# Sumo_Motor_Stepper_DC_Conns.net
KiCad netlist of a schematic drawn in Altium Designer
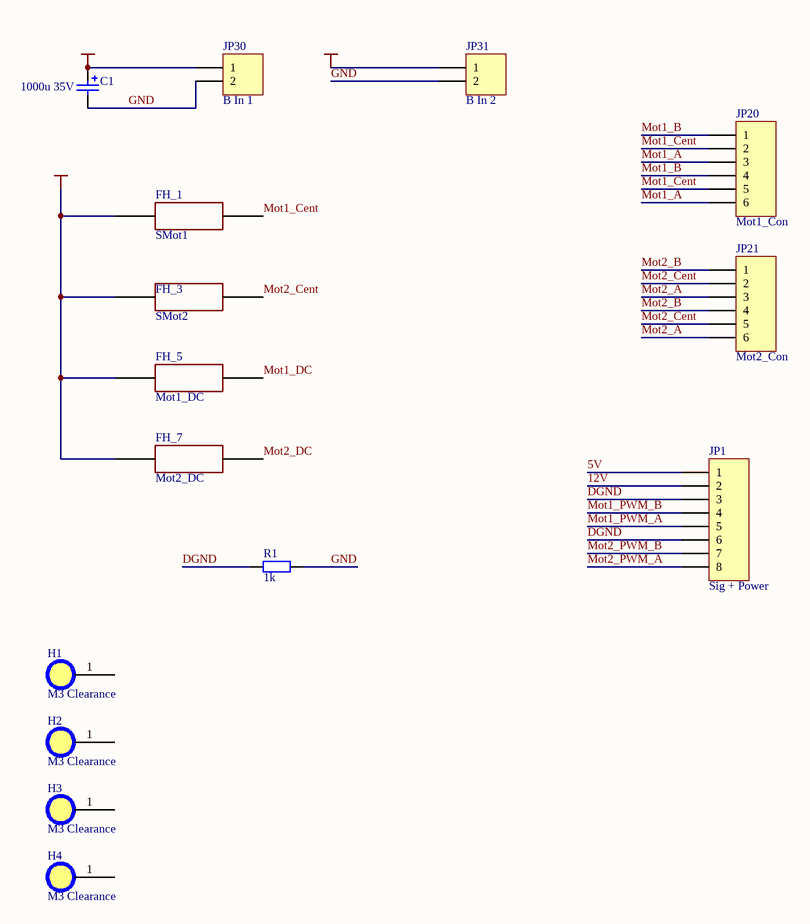
[diagram p0: Sumo_Motor_Stepper_DC_Conns.SCHDOC]

(export (version "E")
  (design (tool "Eeschema 10.0.6"))
  (components
    (comp (ref "C1")
      (value "1000u 35V")
      (footprint "CAPPOL7.5-16")
      (description "Polarized Capacitor (Radial)")
      (fields (field (name "Comment") "Cap Pol1") (field (name "PUBLISHER") "Altium Limited"))
      (libsource (lib "Miscellaneous Devices") (part "Cap Pol1"))
    )
    (comp (ref "FH_1")
      (value "SMot1")
      (footprint "FuseHolder Miniblade")
      (description "Fuse Holder")
      (libsource (lib "Sumo") (part "Fuse_Holder"))
    )
    (comp (ref "FH_3")
      (value "SMot2")
      (footprint "FuseHolder Miniblade")
      (description "Fuse Holder")
      (libsource (lib "Sumo") (part "Fuse_Holder"))
    )
    (comp (ref "FH_5")
      (value "Mot1_DC")
      (footprint "FuseHolder Miniblade")
      (description "Fuse Holder")
      (libsource (lib "") (part "Fuse_Holder_1"))
    )
    (comp (ref "FH_7")
      (value "Mot2_DC")
      (footprint "FuseHolder Miniblade")
      (libsource (lib "") (part "Fuse_Holder_1"))
    )
    (comp (ref "H1")
      (value "M3 Clearance")
      (footprint "M3 Clearance")
      (description "3.2mm ID clearance hole for M3 screw")
      (libsource (lib "Sumo") (part "M3 Clearance hole"))
    )
    (comp (ref "H2")
      (value "M3 Clearance")
      (footprint "M3 Clearance")
      (description "3.2mm ID clearance hole for M3 screw")
      (libsource (lib "Sumo") (part "M3 Clearance hole"))
    )
    (comp (ref "H3")
      (value "M3 Clearance")
      (footprint "M3 Clearance")
      (description "3.2mm ID clearance hole for M3 screw")
      (libsource (lib "Sumo") (part "M3 Clearance hole"))
    )
    (comp (ref "H4")
      (value "M3 Clearance")
      (footprint "M3 Clearance")
      (description "3.2mm ID clearance hole for M3 screw")
      (libsource (lib "Sumo") (part "M3 Clearance hole"))
    )
    (comp (ref "JP1")
      (value "Sig + Power")
      (footprint "PHR 1x8 2mm")
      (description "Header, 8-Pin")
      (fields (field (name "PUBLISHER") "Altium Limited"))
      (libsource (lib "Miscellaneous Connectors") (part "Header 8"))
    )
    (comp (ref "JP20")
      (value "Mot1_Con")
      (footprint "microfit 2x3 3mm")
      (description "Header, 6-Pin")
      (fields (field (name "PUBLISHER") "Altium Limited"))
      (libsource (lib "*") (part "Header 6"))
    )
    (comp (ref "JP21")
      (value "Mot2_Con")
      (footprint "microfit 2x3 3mm")
      (description "Header, 6-Pin")
      (fields (field (name "PUBLISHER") "Altium Limited"))
      (libsource (lib "*") (part "Header 6"))
    )
    (comp (ref "JP30")
      (value "B In 1")
      (footprint "Screw Terminals x 2 x M4")
      (description "Header, 2-Pin")
      (fields (field (name "PUBLISHER") "Altium Limited"))
      (libsource (lib "Miscellaneous Connectors") (part "Header 2"))
    )
    (comp (ref "JP31")
      (value "B In 2")
      (footprint "Mini-Fit Jnr 2x1 4.2mm")
      (description "Header, 2-Pin")
      (fields (field (name "PUBLISHER") "Altium Limited"))
      (libsource (lib "Miscellaneous Connectors") (part "Header 2"))
    )
    (comp (ref "R1")
      (value "1k")
      (footprint "CR2012-0805")
      (description "Semiconductor Resistor")
      (fields (field (name "Comment") "Res Semi") (field (name "PUBLISHER") "Altium Limited"))
      (libsource (lib "Miscellaneous Devices") (part "Res Semi"))
    )
  )
  (nets
    (net (code "1") (name "/5V") (class "Default")
      (node (ref "JP1") (pin "1") (pinfunction "1_1") (pintype "passive"))
    )
    (net (code "2") (name "/12V") (class "Default")
      (node (ref "JP1") (pin "2") (pinfunction "2_2") (pintype "passive"))
    )
    (net (code "3") (name "/DGND") (class "Default")
      (node (ref "JP1") (pin "3") (pinfunction "3_3") (pintype "passive"))
      (node (ref "JP1") (pin "6") (pinfunction "6_6") (pintype "passive"))
      (node (ref "R1") (pin "2") (pinfunction "2_2") (pintype "passive"))
    )
    (net (code "4") (name "/GND") (class "Default")
      (node (ref "C1") (pin "2") (pinfunction "2_2") (pintype "passive"))
      (node (ref "JP30") (pin "2") (pinfunction "2_2") (pintype "passive"))
      (node (ref "JP31") (pin "2") (pinfunction "2_2") (pintype "passive"))
      (node (ref "R1") (pin "1") (pinfunction "1_1") (pintype "passive"))
    )
    (net (code "5") (name "/Mot1_A") (class "Default")
      (node (ref "JP20") (pin "3") (pinfunction "3_3") (pintype "passive"))
    )
    (net (code "6") (name "/Mot1_B") (class "Default")
      (node (ref "JP20") (pin "1") (pinfunction "1_1") (pintype "passive"))
    )
    (net (code "7") (name "/Mot1_Cent") (class "Default")
      (node (ref "FH_1") (pin "2") (pinfunction "2_2") (pintype "passive"))
      (node (ref "JP20") (pin "2") (pinfunction "2_2") (pintype "passive"))
      (node (ref "JP20") (pin "5") (pinfunction "5_5") (pintype "passive"))
    )
    (net (code "8") (name "/Mot1_DC") (class "Default")
      (node (ref "FH_5") (pin "1") (pinfunction "1_1") (pintype "passive"))
    )
    (net (code "9") (name "/Mot1_PWM_A") (class "Default")
      (node (ref "JP1") (pin "5") (pinfunction "5_5") (pintype "passive"))
    )
    (net (code "10") (name "/Mot1_PWM_B") (class "Default")
      (node (ref "JP1") (pin "4") (pinfunction "4_4") (pintype "passive"))
    )
    (net (code "11") (name "/Mot1_~{A}") (class "Default")
      (node (ref "JP20") (pin "6") (pinfunction "6_6") (pintype "passive"))
    )
    (net (code "12") (name "/Mot1_~{B}") (class "Default")
      (node (ref "JP20") (pin "4") (pinfunction "4_4") (pintype "passive"))
    )
    (net (code "13") (name "/Mot2_A") (class "Default")
      (node (ref "JP21") (pin "3") (pinfunction "3_3") (pintype "passive"))
    )
    (net (code "14") (name "/Mot2_B") (class "Default")
      (node (ref "JP21") (pin "1") (pinfunction "1_1") (pintype "passive"))
    )
    (net (code "15") (name "/Mot2_Cent") (class "Default")
      (node (ref "FH_3") (pin "2") (pinfunction "2_2") (pintype "passive"))
      (node (ref "JP21") (pin "2") (pinfunction "2_2") (pintype "passive"))
      (node (ref "JP21") (pin "5") (pinfunction "5_5") (pintype "passive"))
    )
    (net (code "16") (name "/Mot2_DC") (class "Default")
      (node (ref "FH_7") (pin "1") (pinfunction "1_1") (pintype "passive"))
    )
    (net (code "17") (name "/Mot2_PWM_A") (class "Default")
      (node (ref "JP1") (pin "8") (pinfunction "8_8") (pintype "passive"))
    )
    (net (code "18") (name "/Mot2_PWM_B") (class "Default")
      (node (ref "JP1") (pin "7") (pinfunction "7_7") (pintype "passive"))
    )
    (net (code "19") (name "/Mot2_~{A}") (class "Default")
      (node (ref "JP21") (pin "6") (pinfunction "6_6") (pintype "passive"))
    )
    (net (code "20") (name "/Mot2_~{B}") (class "Default")
      (node (ref "JP21") (pin "4") (pinfunction "4_4") (pintype "passive"))
    )
    (net (code "21") (name "VBat") (class "Default")
      (node (ref "C1") (pin "1") (pinfunction "1_1") (pintype "passive"))
      (node (ref "FH_1") (pin "1") (pinfunction "1_1") (pintype "passive"))
      (node (ref "FH_3") (pin "1") (pinfunction "1_1") (pintype "passive"))
      (node (ref "FH_5") (pin "2") (pinfunction "2_2") (pintype "passive"))
      (node (ref "FH_7") (pin "2") (pinfunction "2_2") (pintype "passive"))
      (node (ref "JP30") (pin "1") (pinfunction "1_1") (pintype "passive"))
      (node (ref "JP31") (pin "1") (pinfunction "1_1") (pintype "passive"))
    )
    (net (code "22") (name "unconnected-(H1-Pad1)") (class "Default")
      (node (ref "H1") (pin "1") (pintype "passive"))
    )
    (net (code "23") (name "unconnected-(H2-Pad1)") (class "Default")
      (node (ref "H2") (pin "1") (pintype "passive"))
    )
    (net (code "24") (name "unconnected-(H3-Pad1)") (class "Default")
      (node (ref "H3") (pin "1") (pintype "passive"))
    )
    (net (code "25") (name "unconnected-(H4-Pad1)") (class "Default")
      (node (ref "H4") (pin "1") (pintype "passive"))
    )
  )
)
